# Expansion_Headers.net
KiCad netlist of a schematic drawn in Altium Designer
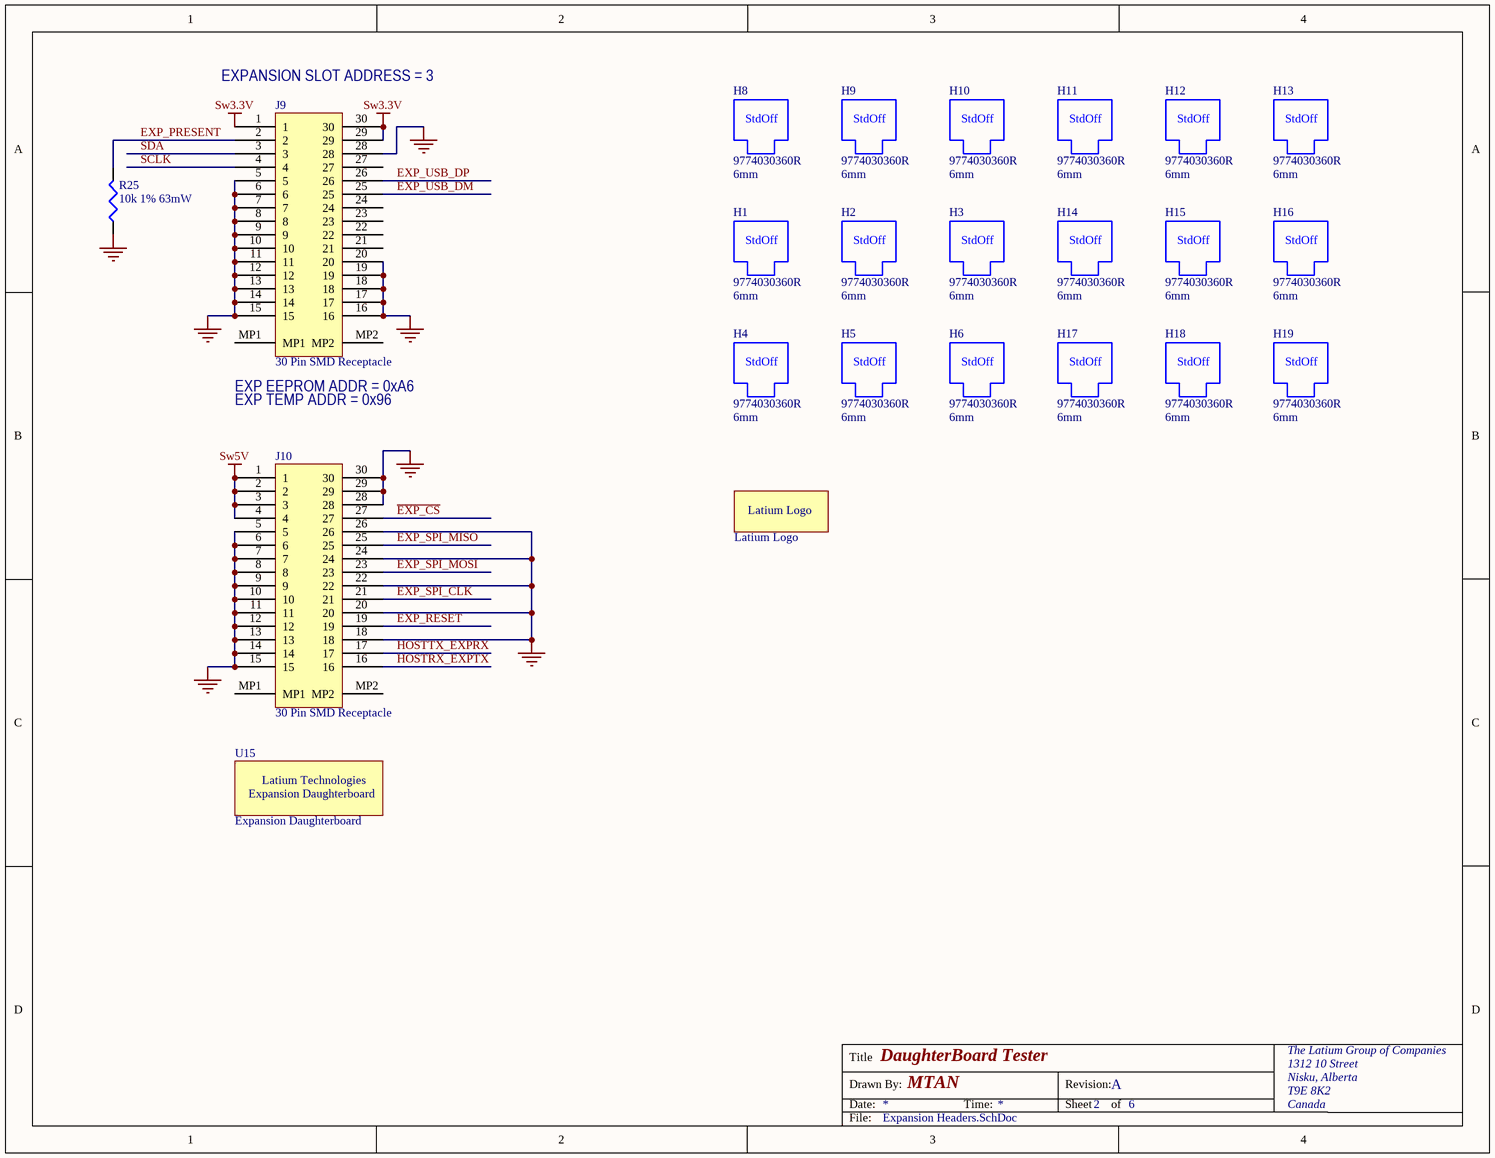
[diagram p0: Expansion Headers.SchDoc]

(export (version "E")
  (design (tool "Eeschema 10.0.6"))
  (components
    (comp (ref "H1")
      (value "9774030360R")
      (footprint "Wurth 9774060360R")
      (description "ROUND STANDOFF M3X0.5 STEEL 6MM")
      (fields
        (field (name "MANUFACTURER") "Wurth Electronics Inc")
        (field (name "MANUFACTURER PART NUMBER") "9774060360R")
        (field (name "HEIGHT") "6mm")
      )
      (libsource (lib "Latium Component Library") (part "SMD M3 Spacer"))
    )
    (comp (ref "H2")
      (value "9774030360R")
      (footprint "Wurth 9774060360R")
      (description "ROUND STANDOFF M3X0.5 STEEL 6MM")
      (fields
        (field (name "MANUFACTURER") "Wurth Electronics Inc")
        (field (name "MANUFACTURER PART NUMBER") "9774060360R")
        (field (name "HEIGHT") "6mm")
      )
      (libsource (lib "Latium Component Library") (part "SMD M3 Spacer"))
    )
    (comp (ref "H3")
      (value "9774030360R")
      (footprint "Wurth 9774060360R")
      (description "ROUND STANDOFF M3X0.5 STEEL 6MM")
      (fields
        (field (name "MANUFACTURER") "Wurth Electronics Inc")
        (field (name "MANUFACTURER PART NUMBER") "9774060360R")
        (field (name "HEIGHT") "6mm")
      )
      (libsource (lib "Latium Component Library") (part "SMD M3 Spacer"))
    )
    (comp (ref "H4")
      (value "9774030360R")
      (footprint "Wurth 9774060360R")
      (description "ROUND STANDOFF M3X0.5 STEEL 6MM")
      (fields
        (field (name "MANUFACTURER") "Wurth Electronics Inc")
        (field (name "MANUFACTURER PART NUMBER") "9774060360R")
        (field (name "HEIGHT") "6mm")
      )
      (libsource (lib "Latium Component Library") (part "SMD M3 Spacer"))
    )
    (comp (ref "H5")
      (value "9774030360R")
      (footprint "Wurth 9774060360R")
      (description "ROUND STANDOFF M3X0.5 STEEL 6MM")
      (fields
        (field (name "MANUFACTURER") "Wurth Electronics Inc")
        (field (name "MANUFACTURER PART NUMBER") "9774060360R")
        (field (name "HEIGHT") "6mm")
      )
      (libsource (lib "Latium Component Library") (part "SMD M3 Spacer"))
    )
    (comp (ref "H6")
      (value "9774030360R")
      (footprint "Wurth 9774060360R")
      (description "ROUND STANDOFF M3X0.5 STEEL 6MM")
      (fields
        (field (name "MANUFACTURER") "Wurth Electronics Inc")
        (field (name "MANUFACTURER PART NUMBER") "9774060360R")
        (field (name "HEIGHT") "6mm")
      )
      (libsource (lib "Latium Component Library") (part "SMD M3 Spacer"))
    )
    (comp (ref "H7")
      (value "Latium Logo")
      (footprint "LatiumLogo")
      (libsource (lib "Latium Component Library") (part "Latium Logo"))
    )
    (comp (ref "H8")
      (value "9774030360R")
      (footprint "Wurth 9774060360R")
      (description "ROUND STANDOFF M3X0.5 STEEL 6MM")
      (fields
        (field (name "MANUFACTURER") "Wurth Electronics Inc")
        (field (name "MANUFACTURER PART NUMBER") "9774060360R")
        (field (name "HEIGHT") "6mm")
      )
      (libsource (lib "Latium Component Library") (part "SMD M3 Spacer"))
    )
    (comp (ref "H9")
      (value "9774030360R")
      (footprint "Wurth 9774060360R")
      (description "ROUND STANDOFF M3X0.5 STEEL 6MM")
      (fields
        (field (name "MANUFACTURER") "Wurth Electronics Inc")
        (field (name "MANUFACTURER PART NUMBER") "9774060360R")
        (field (name "HEIGHT") "6mm")
      )
      (libsource (lib "Latium Component Library") (part "SMD M3 Spacer"))
    )
    (comp (ref "H10")
      (value "9774030360R")
      (footprint "Wurth 9774060360R")
      (description "ROUND STANDOFF M3X0.5 STEEL 6MM")
      (fields
        (field (name "MANUFACTURER") "Wurth Electronics Inc")
        (field (name "MANUFACTURER PART NUMBER") "9774060360R")
        (field (name "HEIGHT") "6mm")
      )
      (libsource (lib "Latium Component Library") (part "SMD M3 Spacer"))
    )
    (comp (ref "H11")
      (value "9774030360R")
      (footprint "Wurth 9774060360R")
      (description "ROUND STANDOFF M3X0.5 STEEL 6MM")
      (fields
        (field (name "MANUFACTURER") "Wurth Electronics Inc")
        (field (name "MANUFACTURER PART NUMBER") "9774060360R")
        (field (name "HEIGHT") "6mm")
      )
      (libsource (lib "Latium Component Library") (part "SMD M3 Spacer"))
    )
    (comp (ref "H12")
      (value "9774030360R")
      (footprint "Wurth 9774060360R")
      (description "ROUND STANDOFF M3X0.5 STEEL 6MM")
      (fields
        (field (name "MANUFACTURER") "Wurth Electronics Inc")
        (field (name "MANUFACTURER PART NUMBER") "9774060360R")
        (field (name "HEIGHT") "6mm")
      )
      (libsource (lib "Latium Component Library") (part "SMD M3 Spacer"))
    )
    (comp (ref "H13")
      (value "9774030360R")
      (footprint "Wurth 9774060360R")
      (description "ROUND STANDOFF M3X0.5 STEEL 6MM")
      (fields
        (field (name "MANUFACTURER") "Wurth Electronics Inc")
        (field (name "MANUFACTURER PART NUMBER") "9774060360R")
        (field (name "HEIGHT") "6mm")
      )
      (libsource (lib "Latium Component Library") (part "SMD M3 Spacer"))
    )
    (comp (ref "H14")
      (value "9774030360R")
      (footprint "Wurth 9774060360R")
      (description "ROUND STANDOFF M3X0.5 STEEL 6MM")
      (fields
        (field (name "MANUFACTURER") "Wurth Electronics Inc")
        (field (name "MANUFACTURER PART NUMBER") "9774060360R")
        (field (name "HEIGHT") "6mm")
      )
      (libsource (lib "Latium Component Library") (part "SMD M3 Spacer"))
    )
    (comp (ref "H15")
      (value "9774030360R")
      (footprint "Wurth 9774060360R")
      (description "ROUND STANDOFF M3X0.5 STEEL 6MM")
      (fields
        (field (name "MANUFACTURER") "Wurth Electronics Inc")
        (field (name "MANUFACTURER PART NUMBER") "9774060360R")
        (field (name "HEIGHT") "6mm")
      )
      (libsource (lib "Latium Component Library") (part "SMD M3 Spacer"))
    )
    (comp (ref "H16")
      (value "9774030360R")
      (footprint "Wurth 9774060360R")
      (description "ROUND STANDOFF M3X0.5 STEEL 6MM")
      (fields
        (field (name "MANUFACTURER") "Wurth Electronics Inc")
        (field (name "MANUFACTURER PART NUMBER") "9774060360R")
        (field (name "HEIGHT") "6mm")
      )
      (libsource (lib "Latium Component Library") (part "SMD M3 Spacer"))
    )
    (comp (ref "H17")
      (value "9774030360R")
      (footprint "Wurth 9774060360R")
      (description "ROUND STANDOFF M3X0.5 STEEL 6MM")
      (fields
        (field (name "MANUFACTURER") "Wurth Electronics Inc")
        (field (name "MANUFACTURER PART NUMBER") "9774060360R")
        (field (name "HEIGHT") "6mm")
      )
      (libsource (lib "Latium Component Library") (part "SMD M3 Spacer"))
    )
    (comp (ref "H18")
      (value "9774030360R")
      (footprint "Wurth 9774060360R")
      (description "ROUND STANDOFF M3X0.5 STEEL 6MM")
      (fields
        (field (name "MANUFACTURER") "Wurth Electronics Inc")
        (field (name "MANUFACTURER PART NUMBER") "9774060360R")
        (field (name "HEIGHT") "6mm")
      )
      (libsource (lib "Latium Component Library") (part "SMD M3 Spacer"))
    )
    (comp (ref "H19")
      (value "9774030360R")
      (footprint "Wurth 9774060360R")
      (description "ROUND STANDOFF M3X0.5 STEEL 6MM")
      (fields
        (field (name "MANUFACTURER") "Wurth Electronics Inc")
        (field (name "MANUFACTURER PART NUMBER") "9774060360R")
        (field (name "HEIGHT") "6mm")
      )
      (libsource (lib "Latium Component Library") (part "SMD M3 Spacer"))
    )
    (comp (ref "J9")
      (value "30 Pin SMD Receptacle")
      (footprint "10132798-031100LF")
      (description "CONN RCPT 30POS SMD GOLD")
      (fields
        (field (name "MANUFACTURER") "Amphenol ICC (FCI)")
        (field (name "MANUFACTURER PART NUMBER") "10132798-031100LF")
      )
      (libsource (lib "Latium Component Library") (part "Amphenol 30 Pos BergStak Plug"))
    )
    (comp (ref "J10")
      (value "30 Pin SMD Receptacle")
      (footprint "10132798-031100LF")
      (description "CONN RCPT 30POS SMD GOLD")
      (fields
        (field (name "MANUFACTURER") "Amphenol ICC (FCI)")
        (field (name "MANUFACTURER PART NUMBER") "10132798-031100LF")
      )
      (libsource (lib "Latium Component Library") (part "Amphenol 30 Pos BergStak Plug"))
    )
    (comp (ref "R25")
      (value "10k 1% 63mW")
      (footprint "RESC1005L")
      (description "Resistor")
      (libsource (lib "Miscellaneous Devices") (part "Res3"))
    )
    (comp (ref "U15")
      (value "Expansion Daughterboard")
      (footprint "Expansion Daughterboard")
      (libsource (lib "Latium Component Library") (part "Expansion Daughterboard"))
    )
  )
  (nets
    (net (code "1") (name "/EXP_PRESENT") (class "Default")
      (node (ref "J9") (pin "2") (pinfunction "2_2") (pintype "passive"))
      (node (ref "R25") (pin "2") (pinfunction "2_2") (pintype "passive"))
    )
    (net (code "2") (name "/EXP_RESET") (class "Default")
      (node (ref "J10") (pin "19") (pinfunction "19_19") (pintype "passive"))
    )
    (net (code "3") (name "/EXP_SPI_CLK") (class "Default")
      (node (ref "J10") (pin "21") (pinfunction "21_21") (pintype "passive"))
    )
    (net (code "4") (name "/EXP_SPI_MISO") (class "Default")
      (node (ref "J10") (pin "25") (pinfunction "25_25") (pintype "passive"))
    )
    (net (code "5") (name "/EXP_SPI_MOSI") (class "Default")
      (node (ref "J10") (pin "23") (pinfunction "23_23") (pintype "passive"))
    )
    (net (code "6") (name "/EXP_USB_DM") (class "Default")
      (node (ref "J9") (pin "25") (pinfunction "25_25") (pintype "passive"))
    )
    (net (code "7") (name "/EXP_USB_DP") (class "Default")
      (node (ref "J9") (pin "26") (pinfunction "26_26") (pintype "passive"))
    )
    (net (code "8") (name "/HOSTRX_EXPTX") (class "Default")
      (node (ref "J10") (pin "16") (pinfunction "16_16") (pintype "passive"))
    )
    (net (code "9") (name "/HOSTTX_EXPRX") (class "Default")
      (node (ref "J10") (pin "17") (pinfunction "17_17") (pintype "passive"))
    )
    (net (code "10") (name "/SCLK") (class "Default")
      (node (ref "J9") (pin "4") (pinfunction "4_4") (pintype "passive"))
    )
    (net (code "11") (name "/SDA") (class "Default")
      (node (ref "J9") (pin "3") (pinfunction "3_3") (pintype "passive"))
    )
    (net (code "12") (name "/~{EXP_CS}") (class "Default")
      (node (ref "J10") (pin "27") (pinfunction "27_27") (pintype "passive"))
    )
    (net (code "13") (name "GND") (class "Default")
      (node (ref "J10") (pin "10") (pinfunction "10_10") (pintype "passive"))
      (node (ref "J10") (pin "11") (pinfunction "11_11") (pintype "passive"))
      (node (ref "J10") (pin "12") (pinfunction "12_12") (pintype "passive"))
      (node (ref "J10") (pin "13") (pinfunction "13_13") (pintype "passive"))
      (node (ref "J10") (pin "14") (pinfunction "14_14") (pintype "passive"))
      (node (ref "J10") (pin "15") (pinfunction "15_15") (pintype "passive"))
      (node (ref "J10") (pin "18") (pinfunction "18_18") (pintype "passive"))
      (node (ref "J10") (pin "20") (pinfunction "20_20") (pintype "passive"))
      (node (ref "J10") (pin "22") (pinfunction "22_22") (pintype "passive"))
      (node (ref "J10") (pin "24") (pinfunction "24_24") (pintype "passive"))
      (node (ref "J10") (pin "26") (pinfunction "26_26") (pintype "passive"))
      (node (ref "J10") (pin "28") (pinfunction "28_28") (pintype "passive"))
      (node (ref "J10") (pin "29") (pinfunction "29_29") (pintype "passive"))
      (node (ref "J10") (pin "30") (pinfunction "30_30") (pintype "passive"))
      (node (ref "J10") (pin "5") (pinfunction "5_5") (pintype "passive"))
      (node (ref "J10") (pin "6") (pinfunction "6_6") (pintype "passive"))
      (node (ref "J10") (pin "7") (pinfunction "7_7") (pintype "passive"))
      (node (ref "J10") (pin "8") (pinfunction "8_8") (pintype "passive"))
      (node (ref "J10") (pin "9") (pinfunction "9_9") (pintype "passive"))
      (node (ref "J9") (pin "10") (pinfunction "10_10") (pintype "passive"))
      (node (ref "J9") (pin "11") (pinfunction "11_11") (pintype "passive"))
      (node (ref "J9") (pin "12") (pinfunction "12_12") (pintype "passive"))
      (node (ref "J9") (pin "13") (pinfunction "13_13") (pintype "passive"))
      (node (ref "J9") (pin "14") (pinfunction "14_14") (pintype "passive"))
      (node (ref "J9") (pin "15") (pinfunction "15_15") (pintype "passive"))
      (node (ref "J9") (pin "16") (pinfunction "16_16") (pintype "passive"))
      (node (ref "J9") (pin "17") (pinfunction "17_17") (pintype "passive"))
      (node (ref "J9") (pin "18") (pinfunction "18_18") (pintype "passive"))
      (node (ref "J9") (pin "19") (pinfunction "19_19") (pintype "passive"))
      (node (ref "J9") (pin "20") (pinfunction "20_20") (pintype "passive"))
      (node (ref "J9") (pin "28") (pinfunction "28_28") (pintype "passive"))
      (node (ref "J9") (pin "5") (pinfunction "5_5") (pintype "passive"))
      (node (ref "J9") (pin "6") (pinfunction "6_6") (pintype "passive"))
      (node (ref "J9") (pin "7") (pinfunction "7_7") (pintype "passive"))
      (node (ref "J9") (pin "8") (pinfunction "8_8") (pintype "passive"))
      (node (ref "J9") (pin "9") (pinfunction "9_9") (pintype "passive"))
      (node (ref "R25") (pin "1") (pinfunction "1_1") (pintype "passive"))
    )
    (net (code "14") (name "Sw3.3V") (class "Default")
      (node (ref "J9") (pin "1") (pinfunction "1_1") (pintype "passive"))
      (node (ref "J9") (pin "29") (pinfunction "29_29") (pintype "passive"))
      (node (ref "J9") (pin "30") (pinfunction "30_30") (pintype "passive"))
    )
    (net (code "15") (name "Sw5V") (class "Default")
      (node (ref "J10") (pin "1") (pinfunction "1_1") (pintype "passive"))
      (node (ref "J10") (pin "2") (pinfunction "2_2") (pintype "passive"))
      (node (ref "J10") (pin "3") (pinfunction "3_3") (pintype "passive"))
      (node (ref "J10") (pin "4") (pinfunction "4_4") (pintype "passive"))
    )
    (net (code "16") (name "unconnected-(J9-Pad21)") (class "Default")
      (node (ref "J9") (pin "21") (pinfunction "21_21") (pintype "passive"))
    )
    (net (code "17") (name "unconnected-(J9-Pad22)") (class "Default")
      (node (ref "J9") (pin "22") (pinfunction "22_22") (pintype "passive"))
    )
    (net (code "18") (name "unconnected-(J9-Pad23)") (class "Default")
      (node (ref "J9") (pin "23") (pinfunction "23_23") (pintype "passive"))
    )
    (net (code "19") (name "unconnected-(J9-Pad24)") (class "Default")
      (node (ref "J9") (pin "24") (pinfunction "24_24") (pintype "passive"))
    )
    (net (code "20") (name "unconnected-(J9-Pad27)") (class "Default")
      (node (ref "J9") (pin "27") (pinfunction "27_27") (pintype "passive"))
    )
    (net (code "21") (name "unconnected-(J9-PadMP1)") (class "Default")
      (node (ref "J9") (pin "MP1") (pinfunction "MP1_MP1") (pintype "passive"))
    )
    (net (code "22") (name "unconnected-(J9-PadMP2)") (class "Default")
      (node (ref "J9") (pin "MP2") (pinfunction "MP2_MP2") (pintype "passive"))
    )
    (net (code "23") (name "unconnected-(J10-PadMP1)") (class "Default")
      (node (ref "J10") (pin "MP1") (pinfunction "MP1_MP1") (pintype "passive"))
    )
    (net (code "24") (name "unconnected-(J10-PadMP2)") (class "Default")
      (node (ref "J10") (pin "MP2") (pinfunction "MP2_MP2") (pintype "passive"))
    )
  )
)
